# ALS-PT19.net
KiCad netlist of a schematic drawn in Altium Designer
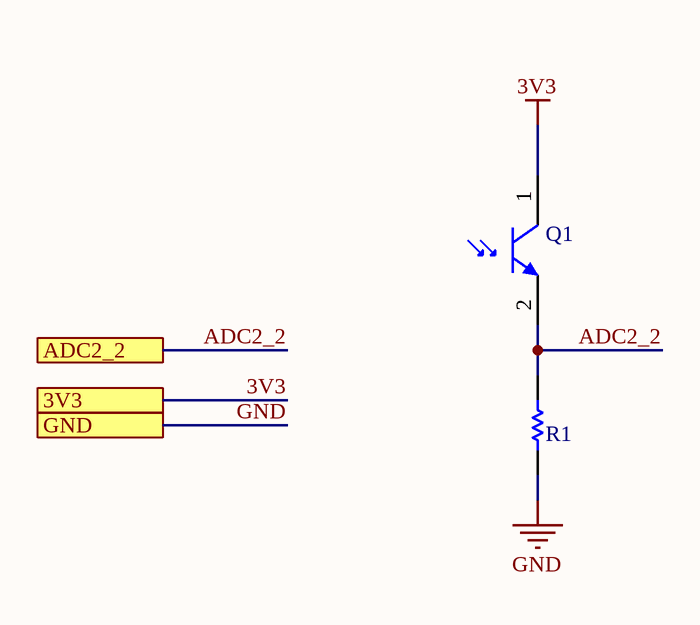
[diagram p0: ALS-PT19.SchDoc]

(export (version "E")
  (design (tool "Eeschema 10.0.6"))
  (components
    (comp (ref "Q1")
      (value "ALS-PT19-315C/L177/TR8")
      (footprint "2-SMD_ALS-PT19")
      (description "Phototransistor 630nm 2-SMD, No Lead")
      (libsource (lib "LIB_FIT") (part "ALS-PT19-315C/L177/TR8"))
    )
    (comp (ref "R1")
      (value "RK73B2ATTD103J")
      (footprint "RESC2013X60X30NL20T20")
      (fields (field (name "MANUFACTURER") "KOA Speer"))
      (libsource (lib "Altium Content Vault") (part "RES"))
    )
  )
  (nets
    (net (code "1") (name "/ADC2_2") (class "Default")
      (node (ref "Q1") (pin "2") (pinfunction "E_2") (pintype "passive"))
      (node (ref "R1") (pin "1") (pinfunction "1_1") (pintype "passive"))
    )
    (net (code "2") (name "3V3") (class "Default")
      (node (ref "Q1") (pin "1") (pinfunction "C_1") (pintype "passive"))
    )
    (net (code "3") (name "GND") (class "Default")
      (node (ref "R1") (pin "2") (pinfunction "2_2") (pintype "passive"))
    )
  )
)
